# design.net
KiCad netlist of a schematic drawn in Altium Designer
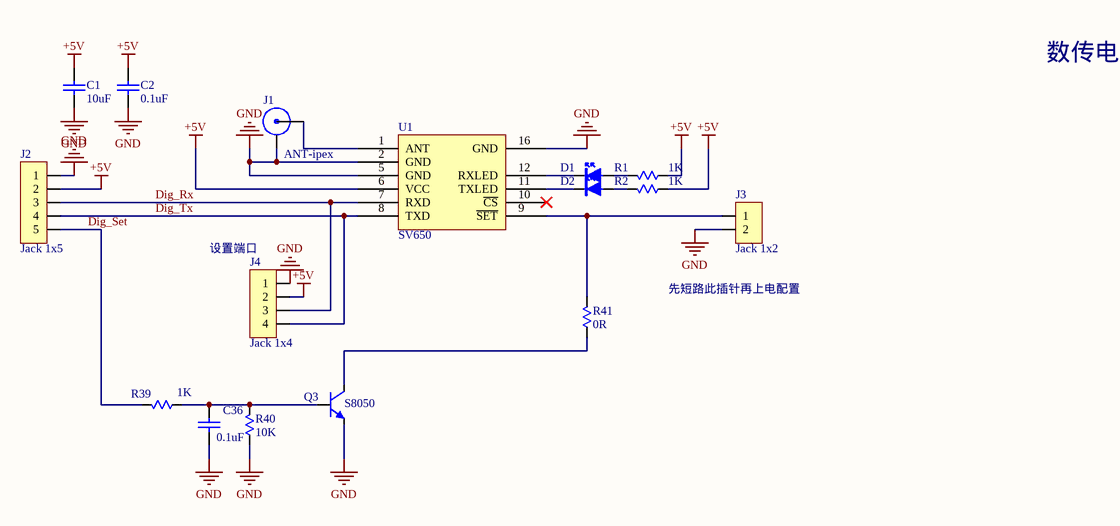
[diagram p0: 海关全向控制器数传转接板.SchDoc]

(export (version "E")
  (design (tool "Eeschema 10.0.6"))
  (components
    (comp (ref "C1") (value "10uF") (footprint "C0603") (libsource (lib "SMD") (part "Cap Semi")))
    (comp (ref "C2") (value "0.1uF") (footprint "C0603") (libsource (lib "SMD") (part "Cap Semi")))
    (comp (ref "C36")
      (value "0.1uF")
      (footprint "C0603")
      (description "CAP")
      (fields (field (name "PUBLISHER") "Altium Limited"))
      (libsource (lib "Passive Components Class") (part "CAP"))
    )
    (comp (ref "D1")
      (value "LED")
      (footprint "LED0603")
      (libsource (lib "Passive Components Class") (part "LED"))
    )
    (comp (ref "D2")
      (value "LED")
      (footprint "LED0603")
      (libsource (lib "Passive Components Class") (part "LED"))
    )
    (comp (ref "J1") (value "ANT-ipex") (footprint "IPEX") (libsource (lib "RLCYDF") (part "ANT-ipex")))
    (comp (ref "J2")
      (value "Jack 1x5")
      (footprint "ZH-5AWD")
      (description "插座")
      (libsource (lib "Connector") (part "Jack 1x5"))
    )
    (comp (ref "J3")
      (value "Jack 1x2")
      (footprint "Jk1*2-2.0")
      (description "插座")
      (libsource (lib "Connector") (part "Jack 1x2"))
    )
    (comp (ref "J4")
      (value "Jack 1x4")
      (footprint "HDR1X4")
      (description "插座")
      (libsource (lib "Connector") (part "Jack 1x4"))
    )
    (comp (ref "Q3")
      (value "S8050")
      (footprint "SOT-23")
      (description "NPN General Purpose Amplifier")
      (fields (field (name "PUBLISHER") "Altium Limited"))
      (libsource (lib "Bdmc4810") (part "NPN"))
    )
    (comp (ref "R1")
      (value "1K")
      (footprint "R0603")
      (description "Resistor")
      (fields (field (name "PUBLISHER") "Altium Limited"))
      (libsource (lib "UP-Robot") (part "Res"))
    )
    (comp (ref "R2")
      (value "1K")
      (footprint "R0603")
      (description "Resistor")
      (fields (field (name "PUBLISHER") "Altium Limited"))
      (libsource (lib "UP-Robot") (part "Res"))
    )
    (comp (ref "R39")
      (value "1K")
      (footprint "R0603")
      (description "Resistor")
      (fields (field (name "PUBLISHER") "Altium Limited"))
      (libsource (lib "Temp") (part "Res"))
    )
    (comp (ref "R40")
      (value "10K")
      (footprint "R0603")
      (description "Resistor")
      (fields (field (name "PUBLISHER") "Altium Limited"))
      (libsource (lib "Temp") (part "Res"))
    )
    (comp (ref "R41")
      (value "0R")
      (footprint "R0603")
      (description "Resistor")
      (fields (field (name "PUBLISHER") "Altium Limited"))
      (libsource (lib "Temp") (part "Res"))
    )
    (comp (ref "U1") (value "SV650") (footprint "SV650") (libsource (lib "Module") (part "SV650")))
  )
  (nets
    (net (code "1") (name "+5V") (class "Default")
      (node (ref "C1") (pin "2") (pinfunction "2_2") (pintype "passive"))
      (node (ref "C2") (pin "2") (pinfunction "2_2") (pintype "passive"))
      (node (ref "J2") (pin "2") (pinfunction "2_2") (pintype "passive"))
      (node (ref "J4") (pin "2") (pinfunction "2_2") (pintype "passive"))
      (node (ref "R1") (pin "1") (pinfunction "1_1") (pintype "passive"))
      (node (ref "R2") (pin "1") (pinfunction "1_1") (pintype "passive"))
      (node (ref "U1") (pin "6") (pinfunction "VCC_6") (pintype "passive"))
    )
    (net (code "2") (name "/Dig_Rx") (class "Default")
      (node (ref "J2") (pin "3") (pinfunction "3_3") (pintype "passive"))
      (node (ref "J4") (pin "3") (pinfunction "3_3") (pintype "passive"))
      (node (ref "U1") (pin "7") (pinfunction "RXD_7") (pintype "passive"))
    )
    (net (code "3") (name "/Dig_Set") (class "Default")
      (node (ref "J2") (pin "5") (pinfunction "5_5") (pintype "passive"))
      (node (ref "R39") (pin "1") (pinfunction "1_1") (pintype "passive"))
    )
    (net (code "4") (name "/Dig_Tx") (class "Default")
      (node (ref "J2") (pin "4") (pinfunction "4_4") (pintype "passive"))
      (node (ref "J4") (pin "4") (pinfunction "4_4") (pintype "passive"))
      (node (ref "U1") (pin "8") (pinfunction "TXD_8") (pintype "passive"))
    )
    (net (code "5") (name "GND") (class "Default")
      (node (ref "C1") (pin "1") (pinfunction "1_1") (pintype "passive"))
      (node (ref "C2") (pin "1") (pinfunction "1_1") (pintype "passive"))
      (node (ref "C36") (pin "1") (pinfunction "1_1") (pintype "passive"))
      (node (ref "J1") (pin "2") (pinfunction "GND_2") (pintype "passive"))
      (node (ref "J2") (pin "1") (pinfunction "1_1") (pintype "passive"))
      (node (ref "J3") (pin "2") (pinfunction "2_2") (pintype "passive"))
      (node (ref "J4") (pin "1") (pinfunction "1_1") (pintype "passive"))
      (node (ref "Q3") (pin "2") (pinfunction "E_2") (pintype "passive"))
      (node (ref "R40") (pin "2") (pinfunction "2_2") (pintype "passive"))
      (node (ref "U1") (pin "16") (pinfunction "GND_16") (pintype "passive"))
      (node (ref "U1") (pin "2") (pinfunction "GND_2") (pintype "passive"))
      (node (ref "U1") (pin "5") (pinfunction "GND_5") (pintype "passive"))
    )
    (net (code "6") (name "Net-(D1-A)") (class "Default")
      (node (ref "D1") (pin "1") (pinfunction "A_1") (pintype "passive"))
      (node (ref "R1") (pin "2") (pinfunction "2_2") (pintype "passive"))
    )
    (net (code "7") (name "Net-(D1-K)") (class "Default")
      (node (ref "D1") (pin "2") (pinfunction "K_2") (pintype "passive"))
      (node (ref "U1") (pin "12") (pinfunction "RXLED_12") (pintype "passive"))
    )
    (net (code "8") (name "Net-(D2-A)") (class "Default")
      (node (ref "D2") (pin "1") (pinfunction "A_1") (pintype "passive"))
      (node (ref "R2") (pin "2") (pinfunction "2_2") (pintype "passive"))
    )
    (net (code "9") (name "Net-(D2-K)") (class "Default")
      (node (ref "D2") (pin "2") (pinfunction "K_2") (pintype "passive"))
      (node (ref "U1") (pin "11") (pinfunction "TXLED_11") (pintype "passive"))
    )
    (net (code "10") (name "Net-(J1-ANT)") (class "Default")
      (node (ref "J1") (pin "1") (pinfunction "ANT_1") (pintype "passive"))
      (node (ref "U1") (pin "1") (pinfunction "ANT_1") (pintype "passive"))
    )
    (net (code "11") (name "Net-(Q3-B)") (class "Default")
      (node (ref "C36") (pin "2") (pinfunction "2_2") (pintype "passive"))
      (node (ref "Q3") (pin "1") (pinfunction "B_1") (pintype "passive"))
      (node (ref "R39") (pin "2") (pinfunction "2_2") (pintype "passive"))
      (node (ref "R40") (pin "1") (pinfunction "1_1") (pintype "passive"))
    )
    (net (code "12") (name "Net-(Q3-C)") (class "Default")
      (node (ref "Q3") (pin "3") (pinfunction "C_3") (pintype "passive"))
      (node (ref "R41") (pin "2") (pinfunction "2_2") (pintype "passive"))
    )
    (net (code "13") (name "Net-(U1-~{SET})") (class "Default")
      (node (ref "J3") (pin "1") (pinfunction "1_1") (pintype "passive"))
      (node (ref "R41") (pin "1") (pinfunction "1_1") (pintype "passive"))
      (node (ref "U1") (pin "9") (pinfunction "~{SET}_9") (pintype "passive"))
    )
    (net (code "14") (name "unconnected-(U1-~{CS}-Pad10)") (class "Default")
      (node (ref "U1") (pin "10") (pinfunction "~{CS}_10") (pintype "passive+no_connect"))
    )
  )
)
